# Otoponic.net
KiCad netlist of a schematic drawn in EAGLE
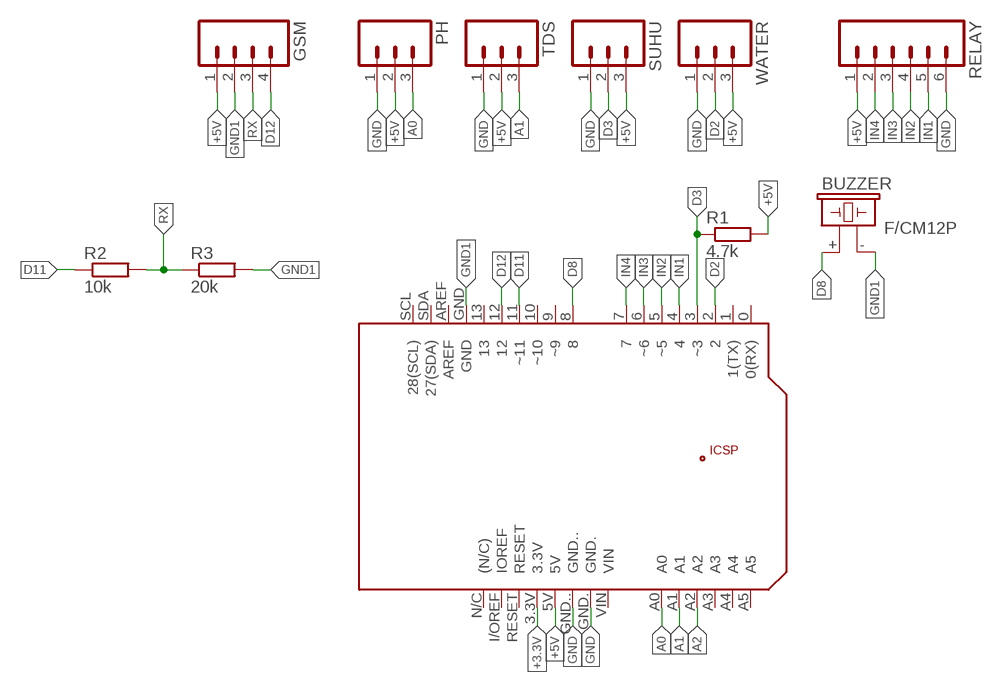
[diagram p0: schematic, sheet 1]

(export (version "E")
  (design (tool "Eeschema 10.0.6"))
  (components
    (comp (ref "BUZZER")
      (value "F/CM12P")
      (footprint "eagle-import:F_CM12P")
      (libsource (lib "eagle-import") (part "F/CM12P"))
    )
    (comp (ref "GSM")
      (value "M04")
      (footprint "eagle-import:04P")
      (libsource (lib "eagle-import") (part "M04"))
    )
    (comp (ref "PCB2")
      (value "ARDUINO_UNO")
      (footprint "eagle-import:ARDUINO_UNO")
      (libsource (lib "eagle-import") (part "ARDUINO_UNO"))
    )
    (comp (ref "PH")
      (value "M03")
      (footprint "eagle-import:03P")
      (libsource (lib "eagle-import") (part "M03"))
    )
    (comp (ref "R1")
      (value "4.7k")
      (footprint "eagle-import:0207_10")
      (libsource (lib "eagle-import") (part "R-EU_0207/10"))
    )
    (comp (ref "R2")
      (value "10k")
      (footprint "eagle-import:0207_10")
      (libsource (lib "eagle-import") (part "R-EU_0207/10"))
    )
    (comp (ref "R3")
      (value "20k")
      (footprint "eagle-import:0207_10")
      (libsource (lib "eagle-import") (part "R-EU_0207/10"))
    )
    (comp (ref "RELAY")
      (value "M06")
      (footprint "eagle-import:06P")
      (libsource (lib "eagle-import") (part "M06"))
    )
    (comp (ref "SUHU")
      (value "M03")
      (footprint "eagle-import:03P")
      (libsource (lib "eagle-import") (part "M03"))
    )
    (comp (ref "TDS")
      (value "M03")
      (footprint "eagle-import:03P")
      (libsource (lib "eagle-import") (part "M03"))
    )
    (comp (ref "WATER")
      (value "M03")
      (footprint "eagle-import:03P")
      (libsource (lib "eagle-import") (part "M03"))
    )
  )
  (nets
    (net (code "1") (name "+3.3V") (class "Default")
      (node (ref "PCB2") (pin "3.3V") (pinfunction "3.3V_3.3V") (pintype "bidirectional"))
    )
    (net (code "2") (name "+5V") (class "Default")
      (node (ref "GSM") (pin "1") (pinfunction "1_1") (pintype "passive"))
      (node (ref "PCB2") (pin "5V") (pinfunction "5V_5V") (pintype "bidirectional"))
      (node (ref "PH") (pin "2") (pinfunction "2_2") (pintype "passive"))
      (node (ref "R1") (pin "2") (pinfunction "2_2") (pintype "passive"))
      (node (ref "RELAY") (pin "1") (pinfunction "1_1") (pintype "passive"))
      (node (ref "SUHU") (pin "3") (pinfunction "3_3") (pintype "passive"))
      (node (ref "TDS") (pin "2") (pinfunction "2_2") (pintype "passive"))
      (node (ref "WATER") (pin "3") (pinfunction "3_3") (pintype "passive"))
    )
    (net (code "3") (name "A0") (class "Default")
      (node (ref "PCB2") (pin "A0") (pinfunction "A0_A0") (pintype "bidirectional"))
      (node (ref "PH") (pin "3") (pinfunction "3_3") (pintype "passive"))
    )
    (net (code "4") (name "A1") (class "Default")
      (node (ref "PCB2") (pin "A1") (pinfunction "A1_A1") (pintype "bidirectional"))
      (node (ref "TDS") (pin "3") (pinfunction "3_3") (pintype "passive"))
    )
    (net (code "5") (name "A2") (class "Default")
      (node (ref "PCB2") (pin "A2") (pinfunction "A2_A2") (pintype "bidirectional"))
    )
    (net (code "6") (name "D2") (class "Default")
      (node (ref "PCB2") (pin "2") (pinfunction "2_2") (pintype "bidirectional"))
      (node (ref "WATER") (pin "2") (pinfunction "2_2") (pintype "passive"))
    )
    (net (code "7") (name "D3") (class "Default")
      (node (ref "PCB2") (pin "3") (pinfunction "~{3}_3") (pintype "bidirectional"))
      (node (ref "R1") (pin "1") (pinfunction "1_1") (pintype "passive"))
      (node (ref "SUHU") (pin "2") (pinfunction "2_2") (pintype "passive"))
    )
    (net (code "8") (name "D8") (class "Default")
      (node (ref "BUZZER") (pin "+") (pinfunction "1_+") (pintype "passive"))
      (node (ref "PCB2") (pin "8") (pinfunction "8_8") (pintype "bidirectional"))
    )
    (net (code "9") (name "D11") (class "Default")
      (node (ref "PCB2") (pin "11") (pinfunction "~{11}_11") (pintype "bidirectional"))
      (node (ref "R2") (pin "1") (pinfunction "1_1") (pintype "passive"))
    )
    (net (code "10") (name "D12") (class "Default")
      (node (ref "GSM") (pin "4") (pinfunction "4_4") (pintype "passive"))
      (node (ref "PCB2") (pin "12") (pinfunction "12_12") (pintype "bidirectional"))
    )
    (net (code "11") (name "GND") (class "Default")
      (node (ref "PCB2") (pin "GND.") (pinfunction "GND._GND.") (pintype "bidirectional"))
      (node (ref "PCB2") (pin "GND..") (pinfunction "GND.._GND..") (pintype "bidirectional"))
      (node (ref "PH") (pin "1") (pinfunction "1_1") (pintype "passive"))
      (node (ref "RELAY") (pin "6") (pinfunction "6_6") (pintype "passive"))
      (node (ref "SUHU") (pin "1") (pinfunction "1_1") (pintype "passive"))
      (node (ref "TDS") (pin "1") (pinfunction "1_1") (pintype "passive"))
      (node (ref "WATER") (pin "1") (pinfunction "1_1") (pintype "passive"))
    )
    (net (code "12") (name "GND1") (class "Default")
      (node (ref "BUZZER") (pin "-") (pinfunction "2_-") (pintype "passive"))
      (node (ref "GSM") (pin "2") (pinfunction "2_2") (pintype "passive"))
      (node (ref "PCB2") (pin "GND") (pinfunction "GND_GND") (pintype "bidirectional"))
      (node (ref "R3") (pin "2") (pinfunction "2_2") (pintype "passive"))
    )
    (net (code "13") (name "IN1") (class "Default")
      (node (ref "PCB2") (pin "4") (pinfunction "4_4") (pintype "bidirectional"))
      (node (ref "RELAY") (pin "5") (pinfunction "5_5") (pintype "passive"))
    )
    (net (code "14") (name "IN2") (class "Default")
      (node (ref "PCB2") (pin "5") (pinfunction "~{5}_5") (pintype "bidirectional"))
      (node (ref "RELAY") (pin "4") (pinfunction "4_4") (pintype "passive"))
    )
    (net (code "15") (name "IN3") (class "Default")
      (node (ref "PCB2") (pin "6") (pinfunction "~{6}_6") (pintype "bidirectional"))
      (node (ref "RELAY") (pin "3") (pinfunction "3_3") (pintype "passive"))
    )
    (net (code "16") (name "IN4") (class "Default")
      (node (ref "PCB2") (pin "7") (pinfunction "7_7") (pintype "bidirectional"))
      (node (ref "RELAY") (pin "2") (pinfunction "2_2") (pintype "passive"))
    )
    (net (code "17") (name "RX") (class "Default")
      (node (ref "GSM") (pin "3") (pinfunction "3_3") (pintype "passive"))
      (node (ref "R2") (pin "2") (pinfunction "2_2") (pintype "passive"))
      (node (ref "R3") (pin "1") (pinfunction "1_1") (pintype "passive"))
    )
    (net (code "18") (name "unconnected-(PCB2-(N{slash}C)-PadN{slash}C)") (class "Default")
      (node (ref "PCB2") (pin "N/C") (pinfunction "(N/C)_N/C") (pintype "bidirectional"))
    )
    (net (code "19") (name "unconnected-(PCB2-0(RX)-Pad0)") (class "Default")
      (node (ref "PCB2") (pin "0") (pinfunction "0(RX)_0") (pintype "bidirectional"))
    )
    (net (code "20") (name "unconnected-(PCB2-1(TX)-Pad1)") (class "Default")
      (node (ref "PCB2") (pin "1") (pinfunction "1(TX)_1") (pintype "bidirectional"))
    )
    (net (code "21") (name "unconnected-(PCB2-27(SDA)-PadSDA)") (class "Default")
      (node (ref "PCB2") (pin "SDA") (pinfunction "27(SDA)_SDA") (pintype "bidirectional"))
    )
    (net (code "22") (name "unconnected-(PCB2-28(SCL)-PadSCL)") (class "Default")
      (node (ref "PCB2") (pin "SCL") (pinfunction "28(SCL)_SCL") (pintype "bidirectional"))
    )
    (net (code "23") (name "unconnected-(PCB2-IOREF-PadI{slash}OREF)") (class "Default")
      (node (ref "PCB2") (pin "I/OREF") (pinfunction "IOREF_I/OREF") (pintype "bidirectional"))
    )
    (net (code "24") (name "unconnected-(PCB2-Pad+5V)") (class "Default")
      (node (ref "PCB2") (pin "+5V") (pinfunction "+5V_+5V") (pintype "bidirectional"))
    )
    (net (code "25") (name "unconnected-(PCB2-Pad13)") (class "Default")
      (node (ref "PCB2") (pin "13") (pinfunction "13_13") (pintype "bidirectional"))
    )
    (net (code "26") (name "unconnected-(PCB2-PadA3)") (class "Default")
      (node (ref "PCB2") (pin "A3") (pinfunction "A3_A3") (pintype "bidirectional"))
    )
    (net (code "27") (name "unconnected-(PCB2-PadA4)") (class "Default")
      (node (ref "PCB2") (pin "A4") (pinfunction "A4_A4") (pintype "bidirectional"))
    )
    (net (code "28") (name "unconnected-(PCB2-PadA5)") (class "Default")
      (node (ref "PCB2") (pin "A5") (pinfunction "A5_A5") (pintype "bidirectional"))
    )
    (net (code "29") (name "unconnected-(PCB2-PadAREF)") (class "Default")
      (node (ref "PCB2") (pin "AREF") (pinfunction "AREF_AREF") (pintype "bidirectional"))
    )
    (net (code "30") (name "unconnected-(PCB2-PadGND_)") (class "Default")
      (node (ref "PCB2") (pin "GND_") (pinfunction "GND__GND_") (pintype "bidirectional"))
    )
    (net (code "31") (name "unconnected-(PCB2-PadMISO)") (class "Default")
      (node (ref "PCB2") (pin "MISO") (pinfunction "MISO_MISO") (pintype "bidirectional"))
    )
    (net (code "32") (name "unconnected-(PCB2-PadMOSI)") (class "Default")
      (node (ref "PCB2") (pin "MOSI") (pinfunction "MOSI_MOSI") (pintype "bidirectional"))
    )
    (net (code "33") (name "unconnected-(PCB2-PadRESET)") (class "Default")
      (node (ref "PCB2") (pin "RESET") (pinfunction "RESET_RESET") (pintype "bidirectional"))
    )
    (net (code "34") (name "unconnected-(PCB2-PadRESET.)") (class "Default")
      (node (ref "PCB2") (pin "RESET.") (pinfunction "RESET._RESET.") (pintype "bidirectional"))
    )
    (net (code "35") (name "unconnected-(PCB2-PadSCK)") (class "Default")
      (node (ref "PCB2") (pin "SCK") (pinfunction "SCK_SCK") (pintype "bidirectional"))
    )
    (net (code "36") (name "unconnected-(PCB2-PadVIN)") (class "Default")
      (node (ref "PCB2") (pin "VIN") (pinfunction "VIN_VIN") (pintype "bidirectional"))
    )
    (net (code "37") (name "unconnected-(PCB2-~{9}-Pad9)") (class "Default")
      (node (ref "PCB2") (pin "9") (pinfunction "~{9}_9") (pintype "bidirectional"))
    )
    (net (code "38") (name "unconnected-(PCB2-~{10}-Pad10)") (class "Default")
      (node (ref "PCB2") (pin "10") (pinfunction "~{10}_10") (pintype "bidirectional"))
    )
  )
)
